# led_shield.net
KiCad netlist of a schematic drawn in EAGLE
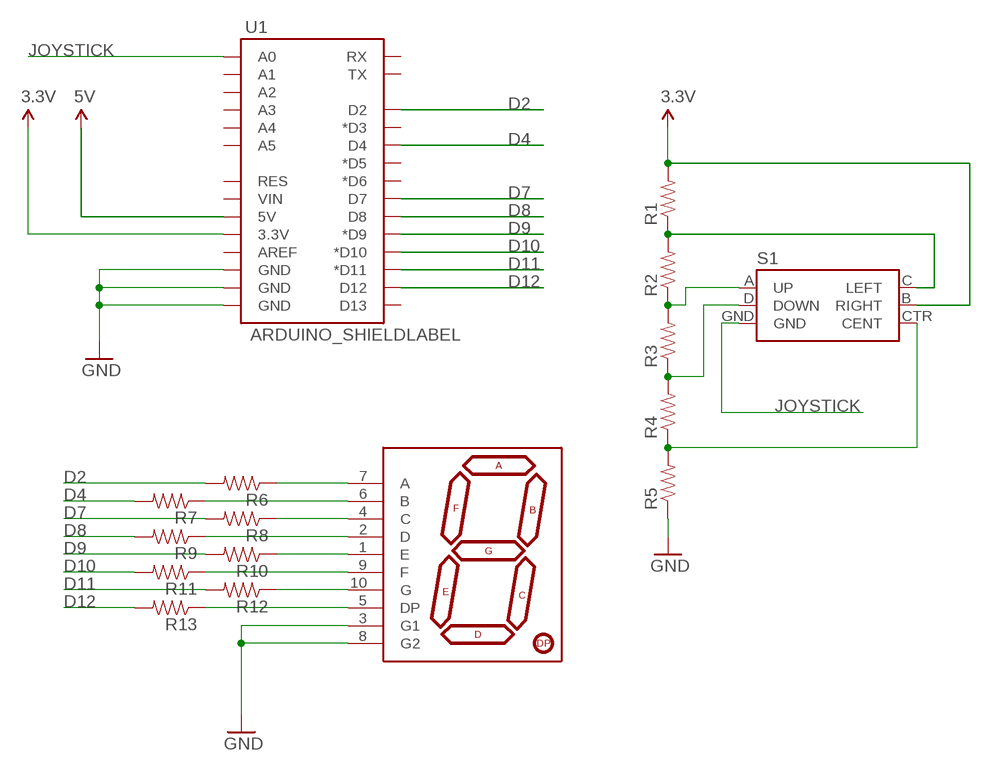
[diagram p0: schematic, sheet 1]

(export (version "E")
  (design (tool "Eeschema 10.0.6"))
  (components
    (comp (ref "R1")
      (value "RESISTOR0805-RES")
      (footprint "eagle-import:0805")
      (libsource (lib "eagle-import") (part "RESISTOR0805-RES"))
    )
    (comp (ref "R2")
      (value "RESISTOR0805-RES")
      (footprint "eagle-import:0805")
      (libsource (lib "eagle-import") (part "RESISTOR0805-RES"))
    )
    (comp (ref "R3")
      (value "RESISTOR0805-RES")
      (footprint "eagle-import:0805")
      (libsource (lib "eagle-import") (part "RESISTOR0805-RES"))
    )
    (comp (ref "R4")
      (value "RESISTOR0805-RES")
      (footprint "eagle-import:0805")
      (libsource (lib "eagle-import") (part "RESISTOR0805-RES"))
    )
    (comp (ref "R5")
      (value "RESISTOR0805-RES")
      (footprint "eagle-import:0805")
      (libsource (lib "eagle-import") (part "RESISTOR0805-RES"))
    )
    (comp (ref "R6")
      (value "RESISTOR0805-RES")
      (footprint "eagle-import:0805")
      (libsource (lib "eagle-import") (part "RESISTOR0805-RES"))
    )
    (comp (ref "R7")
      (value "RESISTOR0805-RES")
      (footprint "eagle-import:0805")
      (libsource (lib "eagle-import") (part "RESISTOR0805-RES"))
    )
    (comp (ref "R8")
      (value "RESISTOR0805-RES")
      (footprint "eagle-import:0805")
      (libsource (lib "eagle-import") (part "RESISTOR0805-RES"))
    )
    (comp (ref "R9")
      (value "RESISTOR0805-RES")
      (footprint "eagle-import:0805")
      (libsource (lib "eagle-import") (part "RESISTOR0805-RES"))
    )
    (comp (ref "R10")
      (value "RESISTOR0805-RES")
      (footprint "eagle-import:0805")
      (libsource (lib "eagle-import") (part "RESISTOR0805-RES"))
    )
    (comp (ref "R11")
      (value "RESISTOR0805-RES")
      (footprint "eagle-import:0805")
      (libsource (lib "eagle-import") (part "RESISTOR0805-RES"))
    )
    (comp (ref "R12")
      (value "RESISTOR0805-RES")
      (footprint "eagle-import:0805")
      (libsource (lib "eagle-import") (part "RESISTOR0805-RES"))
    )
    (comp (ref "R13")
      (value "RESISTOR0805-RES")
      (footprint "eagle-import:0805")
      (libsource (lib "eagle-import") (part "RESISTOR0805-RES"))
    )
    (comp (ref "S1")
      (value "JOYSTICK_MINI")
      (footprint "eagle-import:JOYSTICK_MINI")
      (libsource (lib "eagle-import") (part "JOYSTICK_MINI"))
    )
    (comp (ref "U$1")
      (value "7-SEGMENT-DISPLAY-1\"-RED")
      (footprint "eagle-import:7-SEGMENT-1_PTH")
      (libsource (lib "eagle-import") (part "7-SEGMENT-DISPLAY-1{dblquote}-RED"))
    )
    (comp (ref "U1")
      (value "ARDUINO_SHIELDLABEL")
      (footprint "eagle-import:DUEMILANOVE_SHIELD")
      (libsource (lib "eagle-import") (part "ARDUINO_SHIELDLABEL"))
    )
  )
  (nets
    (net (code "1") (name "/D2") (class "Default")
      (node (ref "R6") (pin "2") (pinfunction "2_2") (pintype "passive"))
      (node (ref "U1") (pin "D2") (pinfunction "D2_D2") (pintype "bidirectional"))
    )
    (net (code "2") (name "/D4") (class "Default")
      (node (ref "R7") (pin "2") (pinfunction "2_2") (pintype "passive"))
      (node (ref "U1") (pin "D4") (pinfunction "D4_D4") (pintype "bidirectional"))
    )
    (net (code "3") (name "/D7") (class "Default")
      (node (ref "R8") (pin "2") (pinfunction "2_2") (pintype "passive"))
      (node (ref "U1") (pin "D7") (pinfunction "D7_D7") (pintype "bidirectional"))
    )
    (net (code "4") (name "/D8") (class "Default")
      (node (ref "R9") (pin "2") (pinfunction "2_2") (pintype "passive"))
      (node (ref "U1") (pin "D8") (pinfunction "D8_D8") (pintype "bidirectional"))
    )
    (net (code "5") (name "/D9") (class "Default")
      (node (ref "R10") (pin "2") (pinfunction "2_2") (pintype "passive"))
      (node (ref "U1") (pin "D9") (pinfunction "*D9_D9") (pintype "bidirectional"))
    )
    (net (code "6") (name "/D10") (class "Default")
      (node (ref "R11") (pin "2") (pinfunction "2_2") (pintype "passive"))
      (node (ref "U1") (pin "D10") (pinfunction "*D10_D10") (pintype "bidirectional"))
    )
    (net (code "7") (name "/D11") (class "Default")
      (node (ref "R12") (pin "2") (pinfunction "2_2") (pintype "passive"))
      (node (ref "U1") (pin "D11") (pinfunction "*D11_D11") (pintype "bidirectional"))
    )
    (net (code "8") (name "/D12") (class "Default")
      (node (ref "R13") (pin "2") (pinfunction "2_2") (pintype "passive"))
      (node (ref "U1") (pin "D12") (pinfunction "D12_D12") (pintype "bidirectional"))
    )
    (net (code "9") (name "/JOYSTICK") (class "Default")
      (node (ref "S1") (pin "GND") (pinfunction "GND_GND") (pintype "bidirectional"))
      (node (ref "U1") (pin "A0") (pinfunction "A0_A0") (pintype "bidirectional"))
    )
    (net (code "10") (name "3.3V") (class "Default")
      (node (ref "R1") (pin "2") (pinfunction "2_2") (pintype "passive"))
      (node (ref "S1") (pin "B") (pinfunction "RIGHT_B") (pintype "bidirectional"))
      (node (ref "U1") (pin "3.3V") (pinfunction "3.3V_3.3V") (pintype "bidirectional"))
    )
    (net (code "11") (name "5V") (class "Default")
      (node (ref "U1") (pin "5V") (pinfunction "5V_5V") (pintype "bidirectional"))
    )
    (net (code "12") (name "GND") (class "Default")
      (node (ref "R5") (pin "1") (pinfunction "1_1") (pintype "passive"))
      (node (ref "U$1") (pin "3") (pinfunction "G1_3") (pintype "bidirectional"))
      (node (ref "U$1") (pin "8") (pinfunction "G2_8") (pintype "bidirectional"))
      (node (ref "U1") (pin "GND@0") (pinfunction "GND_GND@0") (pintype "bidirectional"))
      (node (ref "U1") (pin "GND@1") (pinfunction "GND_GND@1") (pintype "bidirectional"))
      (node (ref "U1") (pin "GND@2") (pinfunction "GND_GND@2") (pintype "bidirectional"))
    )
    (net (code "13") (name "Net-(S1-CENT)") (class "Default")
      (node (ref "R4") (pin "1") (pinfunction "1_1") (pintype "passive"))
      (node (ref "R5") (pin "2") (pinfunction "2_2") (pintype "passive"))
      (node (ref "S1") (pin "CTR") (pinfunction "CENT_CTR") (pintype "bidirectional"))
    )
    (net (code "14") (name "Net-(S1-DOWN)") (class "Default")
      (node (ref "R3") (pin "1") (pinfunction "1_1") (pintype "passive"))
      (node (ref "R4") (pin "2") (pinfunction "2_2") (pintype "passive"))
      (node (ref "S1") (pin "D") (pinfunction "DOWN_D") (pintype "bidirectional"))
    )
    (net (code "15") (name "Net-(S1-LEFT)") (class "Default")
      (node (ref "R1") (pin "1") (pinfunction "1_1") (pintype "passive"))
      (node (ref "R2") (pin "2") (pinfunction "2_2") (pintype "passive"))
      (node (ref "S1") (pin "C") (pinfunction "LEFT_C") (pintype "bidirectional"))
    )
    (net (code "16") (name "Net-(S1-UP)") (class "Default")
      (node (ref "R2") (pin "1") (pinfunction "1_1") (pintype "passive"))
      (node (ref "R3") (pin "2") (pinfunction "2_2") (pintype "passive"))
      (node (ref "S1") (pin "A") (pinfunction "UP_A") (pintype "bidirectional"))
    )
    (net (code "17") (name "Net-(U$1-A)") (class "Default")
      (node (ref "R6") (pin "1") (pinfunction "1_1") (pintype "passive"))
      (node (ref "U$1") (pin "7") (pinfunction "A_7") (pintype "bidirectional"))
    )
    (net (code "18") (name "Net-(U$1-B)") (class "Default")
      (node (ref "R7") (pin "1") (pinfunction "1_1") (pintype "passive"))
      (node (ref "U$1") (pin "6") (pinfunction "B_6") (pintype "bidirectional"))
    )
    (net (code "19") (name "Net-(U$1-C)") (class "Default")
      (node (ref "R8") (pin "1") (pinfunction "1_1") (pintype "passive"))
      (node (ref "U$1") (pin "4") (pinfunction "C_4") (pintype "bidirectional"))
    )
    (net (code "20") (name "Net-(U$1-D)") (class "Default")
      (node (ref "R9") (pin "1") (pinfunction "1_1") (pintype "passive"))
      (node (ref "U$1") (pin "2") (pinfunction "D_2") (pintype "bidirectional"))
    )
    (net (code "21") (name "Net-(U$1-DP)") (class "Default")
      (node (ref "R13") (pin "1") (pinfunction "1_1") (pintype "passive"))
      (node (ref "U$1") (pin "5") (pinfunction "DP_5") (pintype "bidirectional"))
    )
    (net (code "22") (name "Net-(U$1-E)") (class "Default")
      (node (ref "R10") (pin "1") (pinfunction "1_1") (pintype "passive"))
      (node (ref "U$1") (pin "1") (pinfunction "E_1") (pintype "bidirectional"))
    )
    (net (code "23") (name "Net-(U$1-F)") (class "Default")
      (node (ref "R11") (pin "1") (pinfunction "1_1") (pintype "passive"))
      (node (ref "U$1") (pin "9") (pinfunction "F_9") (pintype "bidirectional"))
    )
    (net (code "24") (name "Net-(U$1-G)") (class "Default")
      (node (ref "R12") (pin "1") (pinfunction "1_1") (pintype "passive"))
      (node (ref "U$1") (pin "10") (pinfunction "G_10") (pintype "bidirectional"))
    )
    (net (code "25") (name "unconnected-(U1-*D3-PadD3)") (class "Default")
      (node (ref "U1") (pin "D3") (pinfunction "*D3_D3") (pintype "bidirectional"))
    )
    (net (code "26") (name "unconnected-(U1-*D5-PadD5)") (class "Default")
      (node (ref "U1") (pin "D5") (pinfunction "*D5_D5") (pintype "bidirectional"))
    )
    (net (code "27") (name "unconnected-(U1-*D6-PadD6)") (class "Default")
      (node (ref "U1") (pin "D6") (pinfunction "*D6_D6") (pintype "bidirectional"))
    )
    (net (code "28") (name "unconnected-(U1-PadA1)") (class "Default")
      (node (ref "U1") (pin "A1") (pinfunction "A1_A1") (pintype "bidirectional"))
    )
    (net (code "29") (name "unconnected-(U1-PadA2)") (class "Default")
      (node (ref "U1") (pin "A2") (pinfunction "A2_A2") (pintype "bidirectional"))
    )
    (net (code "30") (name "unconnected-(U1-PadA3)") (class "Default")
      (node (ref "U1") (pin "A3") (pinfunction "A3_A3") (pintype "bidirectional"))
    )
    (net (code "31") (name "unconnected-(U1-PadA4)") (class "Default")
      (node (ref "U1") (pin "A4") (pinfunction "A4_A4") (pintype "bidirectional"))
    )
    (net (code "32") (name "unconnected-(U1-PadA5)") (class "Default")
      (node (ref "U1") (pin "A5") (pinfunction "A5_A5") (pintype "bidirectional"))
    )
    (net (code "33") (name "unconnected-(U1-PadAREF)") (class "Default")
      (node (ref "U1") (pin "AREF") (pinfunction "AREF_AREF") (pintype "bidirectional"))
    )
    (net (code "34") (name "unconnected-(U1-PadD13)") (class "Default")
      (node (ref "U1") (pin "D13") (pinfunction "D13_D13") (pintype "bidirectional"))
    )
    (net (code "35") (name "unconnected-(U1-PadRES)") (class "Default")
      (node (ref "U1") (pin "RES") (pinfunction "RES_RES") (pintype "bidirectional"))
    )
    (net (code "36") (name "unconnected-(U1-PadRX)") (class "Default")
      (node (ref "U1") (pin "RX") (pinfunction "RX_RX") (pintype "bidirectional"))
    )
    (net (code "37") (name "unconnected-(U1-PadTX)") (class "Default")
      (node (ref "U1") (pin "TX") (pinfunction "TX_TX") (pintype "bidirectional"))
    )
    (net (code "38") (name "unconnected-(U1-PadVIN)") (class "Default")
      (node (ref "U1") (pin "VIN") (pinfunction "VIN_VIN") (pintype "bidirectional"))
    )
  )
)
